# schChaves.net
KiCad netlist of a schematic drawn in Altium Designer
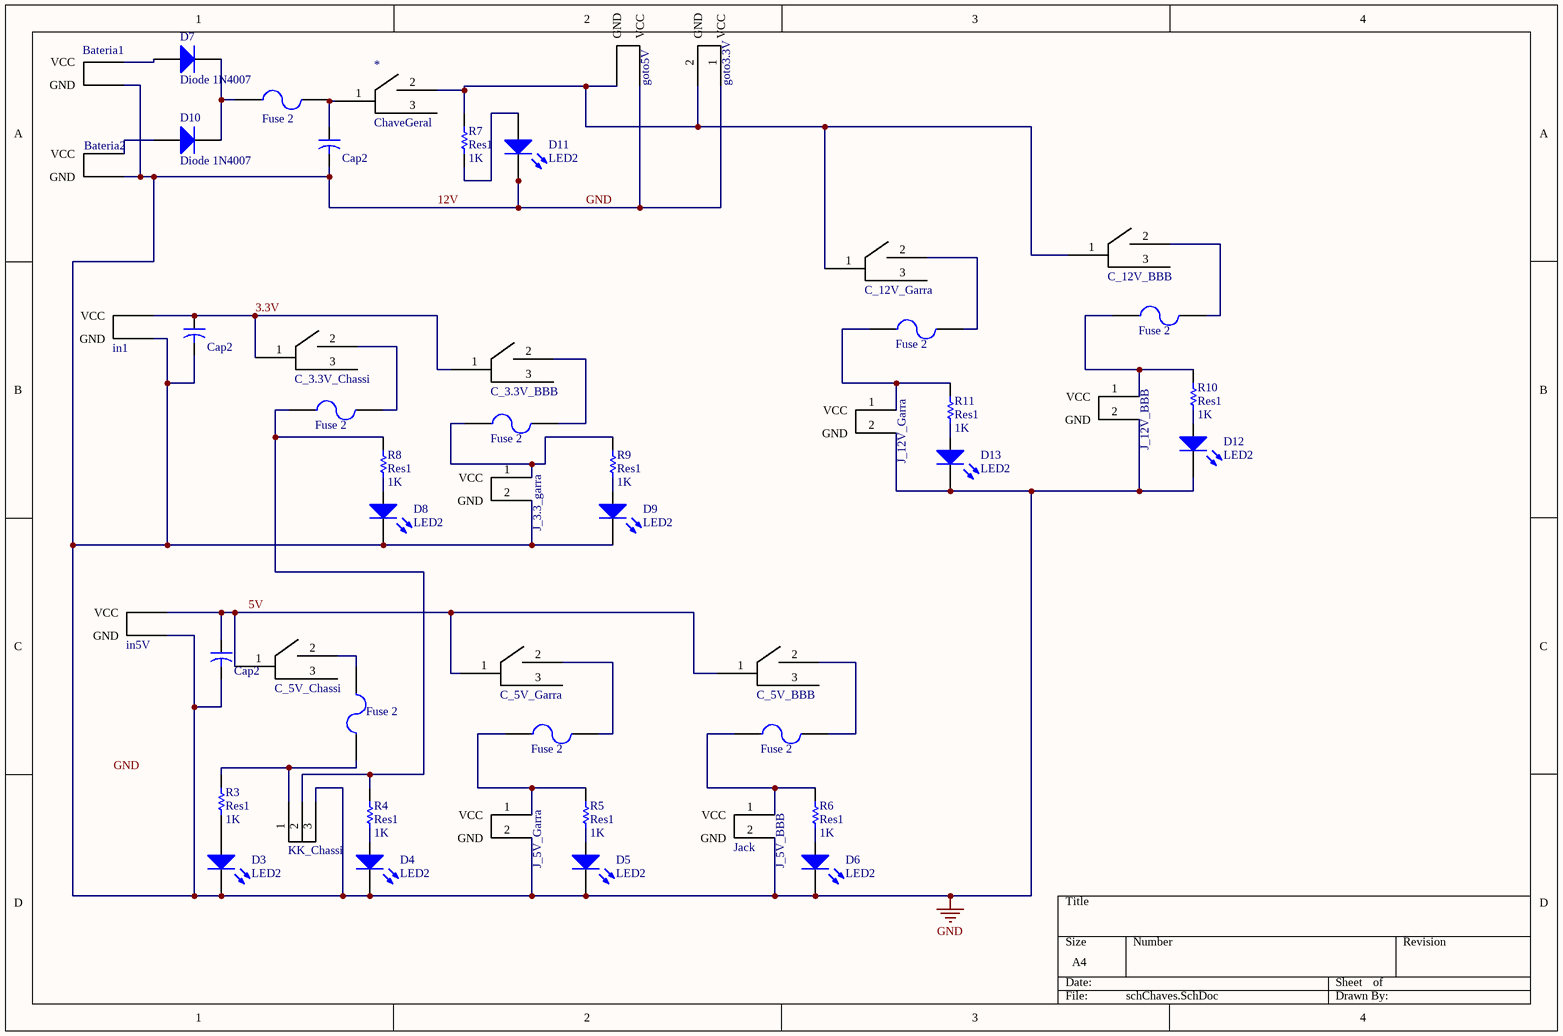
[diagram p0: schChaves.SchDoc]

(export (version "E")
  (design (tool "Eeschema 10.0.6"))
  (components
    (comp (ref "*")
      (value "ChaveGeral")
      (footprint "Chave")
      (libsource (lib "Componentes_Open") (part "Chave"))
    )
    (comp (ref "Bateria1")
      (value "Jack")
      (footprint "JACK J4")
      (libsource (lib "Componentes_Open") (part "Jack"))
    )
    (comp (ref "Bateria2")
      (value "Jack")
      (footprint "JACK J4")
      (libsource (lib "Componentes_Open") (part "Jack"))
    )
    (comp (ref "C_3.3V_BBB")
      (value "Chave")
      (footprint "Chave")
      (libsource (lib "Componentes_Open") (part "Chave"))
    )
    (comp (ref "C_3.3V_Chassi")
      (value "Chave")
      (footprint "Chave")
      (libsource (lib "Componentes_Open") (part "Chave"))
    )
    (comp (ref "C_5V_BBB")
      (value "Chave")
      (footprint "Chave")
      (libsource (lib "Componentes_Open") (part "Chave"))
    )
    (comp (ref "C_5V_Chassi")
      (value "Chave")
      (footprint "Chave")
      (libsource (lib "Componentes_Open") (part "Chave"))
    )
    (comp (ref "C_5V_Garra")
      (value "Chave")
      (footprint "Chave")
      (libsource (lib "Componentes_Open") (part "Chave"))
    )
    (comp (ref "C_12V_BBB")
      (value "Chave")
      (footprint "Chave")
      (libsource (lib "Componentes_Open") (part "Chave"))
    )
    (comp (ref "C_12V_Garra")
      (value "Chave")
      (footprint "Chave")
      (libsource (lib "Componentes_Open") (part "Chave"))
    )
    (comp (ref "C_parrudo")
      (value "Cap2")
      (footprint "CAPR5-4X5")
      (description "Capacitor")
      (fields (field (name "PUBLISHER") "Altium Limited"))
      (libsource (lib "Miscellaneous Devices") (part "Cap2"))
    )
    (comp (ref "C_parrudo1")
      (value "Cap2")
      (footprint "CAPR5-4X5")
      (description "Capacitor")
      (fields (field (name "PUBLISHER") "Altium Limited"))
      (libsource (lib "Miscellaneous Devices") (part "Cap2"))
    )
    (comp (ref "C_parrudo2")
      (value "Cap2")
      (footprint "CAPR5-4X5")
      (description "Capacitor")
      (fields (field (name "PUBLISHER") "Altium Limited"))
      (libsource (lib "Miscellaneous Devices") (part "Cap2"))
    )
    (comp (ref "D3")
      (value "LED2")
      (footprint "2-vias")
      (description "Typical RED, GREEN, YELLOW, AMBER GaAs LED")
      (fields (field (name "PUBLISHER") "Altium Limited"))
      (libsource (lib "Miscellaneous Devices") (part "LED2"))
    )
    (comp (ref "D4")
      (value "LED2")
      (footprint "2-vias")
      (description "Typical RED, GREEN, YELLOW, AMBER GaAs LED")
      (fields (field (name "PUBLISHER") "Altium Limited"))
      (libsource (lib "Miscellaneous Devices") (part "LED2"))
    )
    (comp (ref "D5")
      (value "LED2")
      (footprint "2-vias")
      (description "Typical RED, GREEN, YELLOW, AMBER GaAs LED")
      (fields (field (name "PUBLISHER") "Altium Limited"))
      (libsource (lib "Miscellaneous Devices") (part "LED2"))
    )
    (comp (ref "D6")
      (value "LED2")
      (footprint "2-vias")
      (description "Typical RED, GREEN, YELLOW, AMBER GaAs LED")
      (fields (field (name "PUBLISHER") "Altium Limited"))
      (libsource (lib "Miscellaneous Devices") (part "LED2"))
    )
    (comp (ref "D7")
      (value "Diode 1N4007")
      (footprint "DO-41")
      (description "1 Amp General Purpose Rectifier")
      (fields (field (name "PUBLISHER") "Altium Limited"))
      (libsource (lib "Miscellaneous Devices") (part "Diode 1N4007"))
    )
    (comp (ref "D8")
      (value "LED2")
      (footprint "2-vias")
      (description "Typical RED, GREEN, YELLOW, AMBER GaAs LED")
      (fields (field (name "PUBLISHER") "Altium Limited"))
      (libsource (lib "Miscellaneous Devices") (part "LED2"))
    )
    (comp (ref "D9")
      (value "LED2")
      (footprint "2-vias")
      (description "Typical RED, GREEN, YELLOW, AMBER GaAs LED")
      (fields (field (name "PUBLISHER") "Altium Limited"))
      (libsource (lib "Miscellaneous Devices") (part "LED2"))
    )
    (comp (ref "D10")
      (value "Diode 1N4007")
      (footprint "DO-41")
      (description "1 Amp General Purpose Rectifier")
      (fields (field (name "PUBLISHER") "Altium Limited"))
      (libsource (lib "Miscellaneous Devices") (part "Diode 1N4007"))
    )
    (comp (ref "D11")
      (value "LED2")
      (footprint "2-vias")
      (description "Typical RED, GREEN, YELLOW, AMBER GaAs LED")
      (fields (field (name "PUBLISHER") "Altium Limited"))
      (libsource (lib "Miscellaneous Devices") (part "LED2"))
    )
    (comp (ref "D12")
      (value "LED2")
      (footprint "2-vias")
      (description "Typical RED, GREEN, YELLOW, AMBER GaAs LED")
      (fields (field (name "PUBLISHER") "Altium Limited"))
      (libsource (lib "Miscellaneous Devices") (part "LED2"))
    )
    (comp (ref "D13")
      (value "LED2")
      (footprint "2-vias")
      (description "Typical RED, GREEN, YELLOW, AMBER GaAs LED")
      (fields (field (name "PUBLISHER") "Altium Limited"))
      (libsource (lib "Miscellaneous Devices") (part "LED2"))
    )
    (comp (ref "F1")
      (value "Fuse 2")
      (footprint "AXIAL-0.9")
      (description "Fuse")
      (fields (field (name "PUBLISHER") "Altium Limited"))
      (libsource (lib "Miscellaneous Devices") (part "Fuse 2"))
    )
    (comp (ref "F2")
      (value "Fuse 2")
      (footprint "AXIAL-0.9")
      (description "Fuse")
      (fields (field (name "PUBLISHER") "Altium Limited"))
      (libsource (lib "Miscellaneous Devices") (part "Fuse 2"))
    )
    (comp (ref "F3")
      (value "Fuse 2")
      (footprint "AXIAL-0.9")
      (description "Fuse")
      (fields (field (name "PUBLISHER") "Altium Limited"))
      (libsource (lib "Miscellaneous Devices") (part "Fuse 2"))
    )
    (comp (ref "F4")
      (value "Fuse 2")
      (footprint "AXIAL-0.9")
      (description "Fuse")
      (fields (field (name "PUBLISHER") "Altium Limited"))
      (libsource (lib "Miscellaneous Devices") (part "Fuse 2"))
    )
    (comp (ref "F5")
      (value "Fuse 2")
      (footprint "AXIAL-0.9")
      (description "Fuse")
      (fields (field (name "PUBLISHER") "Altium Limited"))
      (libsource (lib "Miscellaneous Devices") (part "Fuse 2"))
    )
    (comp (ref "F6")
      (value "Fuse 2")
      (footprint "AXIAL-0.9")
      (description "Fuse")
      (fields (field (name "PUBLISHER") "Altium Limited"))
      (libsource (lib "Miscellaneous Devices") (part "Fuse 2"))
    )
    (comp (ref "F7")
      (value "Fuse 2")
      (footprint "AXIAL-0.9")
      (description "Fuse")
      (fields (field (name "PUBLISHER") "Altium Limited"))
      (libsource (lib "Miscellaneous Devices") (part "Fuse 2"))
    )
    (comp (ref "F8")
      (value "Fuse 2")
      (footprint "AXIAL-0.9")
      (description "Fuse")
      (fields (field (name "PUBLISHER") "Altium Limited"))
      (libsource (lib "Miscellaneous Devices") (part "Fuse 2"))
    )
    (comp (ref "goto3.3V") (value "Jack") (footprint "JACK J4") (libsource (lib "") (part "Jack_1")))
    (comp (ref "goto5V")
      (value "Jack")
      (footprint "JACK J4")
      (libsource (lib "Componentes_Open") (part "Jack"))
    )
    (comp (ref "in1") (value "Jack") (footprint "JACK J4") (libsource (lib "Componentes_Open") (part "Jack")))
    (comp (ref "in5V")
      (value "Jack")
      (footprint "JACK J4")
      (libsource (lib "Componentes_Open") (part "Jack"))
    )
    (comp (ref "J_3.3_garra") (value "Jack") (footprint "JACK J4") (libsource (lib "") (part "Jack_1")))
    (comp (ref "J_5V_BBB") (value "Jack") (footprint "JACK J4") (libsource (lib "") (part "Jack_1")))
    (comp (ref "J_5V_Garra") (value "Jack") (footprint "JACK J4") (libsource (lib "") (part "Jack_1")))
    (comp (ref "J_12V_BBB") (value "Jack") (footprint "JACK J4") (libsource (lib "") (part "Jack_1")))
    (comp (ref "J_12V_Garra") (value "Jack") (footprint "JACK J4") (libsource (lib "") (part "Jack_1")))
    (comp (ref "KK_Chassi")
      (value "KK3")
      (footprint "3-vias")
      (libsource (lib "Componentes_Open") (part "KK3Vias"))
    )
    (comp (ref "R3")
      (value "Res1")
      (footprint "AXIAL-0.3")
      (description "Resistor")
      (fields (field (name "ALTIUM_VALUE") "1K") (field (name "PUBLISHER") "Altium Limited"))
      (libsource (lib "Miscellaneous Devices") (part "Res1"))
    )
    (comp (ref "R4")
      (value "Res1")
      (footprint "AXIAL-0.3")
      (description "Resistor")
      (fields (field (name "ALTIUM_VALUE") "1K") (field (name "PUBLISHER") "Altium Limited"))
      (libsource (lib "Miscellaneous Devices") (part "Res1"))
    )
    (comp (ref "R5")
      (value "Res1")
      (footprint "AXIAL-0.3")
      (description "Resistor")
      (fields (field (name "ALTIUM_VALUE") "1K") (field (name "PUBLISHER") "Altium Limited"))
      (libsource (lib "Miscellaneous Devices") (part "Res1"))
    )
    (comp (ref "R6")
      (value "Res1")
      (footprint "AXIAL-0.3")
      (description "Resistor")
      (fields (field (name "ALTIUM_VALUE") "1K") (field (name "PUBLISHER") "Altium Limited"))
      (libsource (lib "Miscellaneous Devices") (part "Res1"))
    )
    (comp (ref "R7")
      (value "Res1")
      (footprint "AXIAL-0.3")
      (description "Resistor")
      (fields (field (name "ALTIUM_VALUE") "1K") (field (name "PUBLISHER") "Altium Limited"))
      (libsource (lib "Miscellaneous Devices") (part "Res1"))
    )
    (comp (ref "R8")
      (value "Res1")
      (footprint "AXIAL-0.3")
      (description "Resistor")
      (fields (field (name "ALTIUM_VALUE") "1K") (field (name "PUBLISHER") "Altium Limited"))
      (libsource (lib "Miscellaneous Devices") (part "Res1"))
    )
    (comp (ref "R9")
      (value "Res1")
      (footprint "AXIAL-0.3")
      (description "Resistor")
      (fields (field (name "ALTIUM_VALUE") "1K") (field (name "PUBLISHER") "Altium Limited"))
      (libsource (lib "Miscellaneous Devices") (part "Res1"))
    )
    (comp (ref "R10")
      (value "Res1")
      (footprint "AXIAL-0.3")
      (description "Resistor")
      (fields (field (name "ALTIUM_VALUE") "1K") (field (name "PUBLISHER") "Altium Limited"))
      (libsource (lib "Miscellaneous Devices") (part "Res1"))
    )
    (comp (ref "R11")
      (value "Res1")
      (footprint "AXIAL-0.3")
      (description "Resistor")
      (fields (field (name "ALTIUM_VALUE") "1K") (field (name "PUBLISHER") "Altium Limited"))
      (libsource (lib "Miscellaneous Devices") (part "Res1"))
    )
  )
  (nets
    (net (code "1") (name "/3.3V") (class "Default")
      (node (ref "C_3.3V_BBB") (pin "1") (pinfunction "Comum_1") (pintype "passive"))
      (node (ref "C_3.3V_Chassi") (pin "1") (pinfunction "Comum_1") (pintype "passive"))
      (node (ref "C_parrudo1") (pin "1") (pinfunction "1_1") (pintype "passive"))
      (node (ref "in1") (pin "1") (pinfunction "VCC_1") (pintype "passive"))
    )
    (net (code "2") (name "/5V") (class "Default")
      (node (ref "C_5V_BBB") (pin "1") (pinfunction "Comum_1") (pintype "passive"))
      (node (ref "C_5V_Chassi") (pin "1") (pinfunction "Comum_1") (pintype "passive"))
      (node (ref "C_5V_Garra") (pin "1") (pinfunction "Comum_1") (pintype "passive"))
      (node (ref "C_parrudo2") (pin "1") (pinfunction "1_1") (pintype "passive"))
      (node (ref "in5V") (pin "1") (pinfunction "VCC_1") (pintype "passive"))
    )
    (net (code "3") (name "GND") (class "Default")
      (node (ref "Bateria1") (pin "2") (pinfunction "GND_2") (pintype "passive"))
      (node (ref "Bateria2") (pin "2") (pinfunction "GND_2") (pintype "passive"))
      (node (ref "C_parrudo") (pin "2") (pinfunction "2_2") (pintype "passive"))
      (node (ref "C_parrudo1") (pin "2") (pinfunction "2_2") (pintype "passive"))
      (node (ref "C_parrudo2") (pin "2") (pinfunction "2_2") (pintype "passive"))
      (node (ref "D11") (pin "2") (pinfunction "K_2") (pintype "passive"))
      (node (ref "D12") (pin "2") (pinfunction "K_2") (pintype "passive"))
      (node (ref "D13") (pin "2") (pinfunction "K_2") (pintype "passive"))
      (node (ref "D3") (pin "2") (pinfunction "K_2") (pintype "passive"))
      (node (ref "D4") (pin "2") (pinfunction "K_2") (pintype "passive"))
      (node (ref "D5") (pin "2") (pinfunction "K_2") (pintype "passive"))
      (node (ref "D6") (pin "2") (pinfunction "K_2") (pintype "passive"))
      (node (ref "D8") (pin "2") (pinfunction "K_2") (pintype "passive"))
      (node (ref "D9") (pin "2") (pinfunction "K_2") (pintype "passive"))
      (node (ref "J_12V_BBB") (pin "2") (pinfunction "GND_2") (pintype "passive"))
      (node (ref "J_12V_Garra") (pin "2") (pinfunction "GND_2") (pintype "passive"))
      (node (ref "J_3.3_garra") (pin "2") (pinfunction "GND_2") (pintype "passive"))
      (node (ref "J_5V_BBB") (pin "2") (pinfunction "GND_2") (pintype "passive"))
      (node (ref "J_5V_Garra") (pin "2") (pinfunction "GND_2") (pintype "passive"))
      (node (ref "KK_Chassi") (pin "3") (pinfunction "3_3") (pintype "passive"))
      (node (ref "goto3.3V") (pin "1") (pinfunction "VCC_1") (pintype "passive"))
      (node (ref "goto5V") (pin "1") (pinfunction "VCC_1") (pintype "passive"))
      (node (ref "in1") (pin "2") (pinfunction "GND_2") (pintype "passive"))
      (node (ref "in5V") (pin "2") (pinfunction "GND_2") (pintype "passive"))
    )
    (net (code "4") (name "Net-(*-Comum)") (class "Default")
      (node (ref "*") (pin "1") (pinfunction "Comum_1") (pintype "passive"))
      (node (ref "C_parrudo") (pin "1") (pinfunction "1_1") (pintype "passive"))
      (node (ref "F1") (pin "2") (pinfunction "2_2") (pintype "passive"))
    )
    (net (code "5") (name "Net-(*-N.A.)") (class "Default")
      (node (ref "*") (pin "2") (pinfunction "N.A._2") (pintype "passive"))
      (node (ref "C_12V_BBB") (pin "1") (pinfunction "Comum_1") (pintype "passive"))
      (node (ref "C_12V_Garra") (pin "1") (pinfunction "Comum_1") (pintype "passive"))
      (node (ref "R7") (pin "2") (pinfunction "2_2") (pintype "passive"))
      (node (ref "goto3.3V") (pin "2") (pinfunction "GND_2") (pintype "passive"))
      (node (ref "goto5V") (pin "2") (pinfunction "GND_2") (pintype "passive"))
    )
    (net (code "6") (name "Net-(Bateria1-VCC)") (class "Default")
      (node (ref "Bateria1") (pin "1") (pinfunction "VCC_1") (pintype "passive"))
      (node (ref "D7") (pin "1") (pinfunction "A_1") (pintype "passive"))
    )
    (net (code "7") (name "Net-(Bateria2-VCC)") (class "Default")
      (node (ref "Bateria2") (pin "1") (pinfunction "VCC_1") (pintype "passive"))
      (node (ref "D10") (pin "1") (pinfunction "A_1") (pintype "passive"))
    )
    (net (code "8") (name "Net-(C_3.3V_BBB-N.A.)") (class "Default")
      (node (ref "C_3.3V_BBB") (pin "2") (pinfunction "N.A._2") (pintype "passive"))
      (node (ref "F3") (pin "2") (pinfunction "2_2") (pintype "passive"))
    )
    (net (code "9") (name "Net-(C_3.3V_Chassi-N.A.)") (class "Default")
      (node (ref "C_3.3V_Chassi") (pin "2") (pinfunction "N.A._2") (pintype "passive"))
      (node (ref "F2") (pin "2") (pinfunction "2_2") (pintype "passive"))
    )
    (net (code "10") (name "Net-(C_5V_BBB-N.A.)") (class "Default")
      (node (ref "C_5V_BBB") (pin "2") (pinfunction "N.A._2") (pintype "passive"))
      (node (ref "F6") (pin "2") (pinfunction "2_2") (pintype "passive"))
    )
    (net (code "11") (name "Net-(C_5V_Chassi-N.A.)") (class "Default")
      (node (ref "C_5V_Chassi") (pin "2") (pinfunction "N.A._2") (pintype "passive"))
      (node (ref "F4") (pin "1") (pinfunction "1_1") (pintype "passive"))
    )
    (net (code "12") (name "Net-(C_5V_Garra-N.A.)") (class "Default")
      (node (ref "C_5V_Garra") (pin "2") (pinfunction "N.A._2") (pintype "passive"))
      (node (ref "F5") (pin "2") (pinfunction "2_2") (pintype "passive"))
    )
    (net (code "13") (name "Net-(C_12V_BBB-N.A.)") (class "Default")
      (node (ref "C_12V_BBB") (pin "2") (pinfunction "N.A._2") (pintype "passive"))
      (node (ref "F7") (pin "2") (pinfunction "2_2") (pintype "passive"))
    )
    (net (code "14") (name "Net-(C_12V_Garra-N.A.)") (class "Default")
      (node (ref "C_12V_Garra") (pin "2") (pinfunction "N.A._2") (pintype "passive"))
      (node (ref "F8") (pin "2") (pinfunction "2_2") (pintype "passive"))
    )
    (net (code "15") (name "Net-(D3-A)") (class "Default")
      (node (ref "D3") (pin "1") (pinfunction "A_1") (pintype "passive"))
      (node (ref "R3") (pin "1") (pinfunction "1_1") (pintype "passive"))
    )
    (net (code "16") (name "Net-(D4-A)") (class "Default")
      (node (ref "D4") (pin "1") (pinfunction "A_1") (pintype "passive"))
      (node (ref "R4") (pin "1") (pinfunction "1_1") (pintype "passive"))
    )
    (net (code "17") (name "Net-(D5-A)") (class "Default")
      (node (ref "D5") (pin "1") (pinfunction "A_1") (pintype "passive"))
      (node (ref "R5") (pin "1") (pinfunction "1_1") (pintype "passive"))
    )
    (net (code "18") (name "Net-(D6-A)") (class "Default")
      (node (ref "D6") (pin "1") (pinfunction "A_1") (pintype "passive"))
      (node (ref "R6") (pin "1") (pinfunction "1_1") (pintype "passive"))
    )
    (net (code "19") (name "Net-(D8-A)") (class "Default")
      (node (ref "D8") (pin "1") (pinfunction "A_1") (pintype "passive"))
      (node (ref "R8") (pin "1") (pinfunction "1_1") (pintype "passive"))
    )
    (net (code "20") (name "Net-(D9-A)") (class "Default")
      (node (ref "D9") (pin "1") (pinfunction "A_1") (pintype "passive"))
      (node (ref "R9") (pin "1") (pinfunction "1_1") (pintype "passive"))
    )
    (net (code "21") (name "Net-(D10-K)") (class "Default")
      (node (ref "D10") (pin "2") (pinfunction "K_2") (pintype "passive"))
      (node (ref "D7") (pin "2") (pinfunction "K_2") (pintype "passive"))
      (node (ref "F1") (pin "1") (pinfunction "1_1") (pintype "passive"))
    )
    (net (code "22") (name "Net-(D11-A)") (class "Default")
      (node (ref "D11") (pin "1") (pinfunction "A_1") (pintype "passive"))
      (node (ref "R7") (pin "1") (pinfunction "1_1") (pintype "passive"))
    )
    (net (code "23") (name "Net-(D12-A)") (class "Default")
      (node (ref "D12") (pin "1") (pinfunction "A_1") (pintype "passive"))
      (node (ref "R10") (pin "1") (pinfunction "1_1") (pintype "passive"))
    )
    (net (code "24") (name "Net-(D13-A)") (class "Default")
      (node (ref "D13") (pin "1") (pinfunction "A_1") (pintype "passive"))
      (node (ref "R11") (pin "1") (pinfunction "1_1") (pintype "passive"))
    )
    (net (code "25") (name "Net-(F2-Pad1)") (class "Default")
      (node (ref "F2") (pin "1") (pinfunction "1_1") (pintype "passive"))
      (node (ref "KK_Chassi") (pin "2") (pinfunction "2_2") (pintype "passive"))
      (node (ref "R4") (pin "2") (pinfunction "2_2") (pintype "passive"))
      (node (ref "R8") (pin "2") (pinfunction "2_2") (pintype "passive"))
    )
    (net (code "26") (name "Net-(F4-Pad2)") (class "Default")
      (node (ref "F4") (pin "2") (pinfunction "2_2") (pintype "passive"))
      (node (ref "KK_Chassi") (pin "1") (pinfunction "1_1") (pintype "passive"))
      (node (ref "R3") (pin "2") (pinfunction "2_2") (pintype "passive"))
    )
    (net (code "27") (name "Net-(J_3.3_garra-VCC)") (class "Default")
      (node (ref "F3") (pin "1") (pinfunction "1_1") (pintype "passive"))
      (node (ref "J_3.3_garra") (pin "1") (pinfunction "VCC_1") (pintype "passive"))
      (node (ref "R9") (pin "2") (pinfunction "2_2") (pintype "passive"))
    )
    (net (code "28") (name "Net-(J_5V_BBB-VCC)") (class "Default")
      (node (ref "F6") (pin "1") (pinfunction "1_1") (pintype "passive"))
      (node (ref "J_5V_BBB") (pin "1") (pinfunction "VCC_1") (pintype "passive"))
      (node (ref "R6") (pin "2") (pinfunction "2_2") (pintype "passive"))
    )
    (net (code "29") (name "Net-(J_5V_Garra-VCC)") (class "Default")
      (node (ref "F5") (pin "1") (pinfunction "1_1") (pintype "passive"))
      (node (ref "J_5V_Garra") (pin "1") (pinfunction "VCC_1") (pintype "passive"))
      (node (ref "R5") (pin "2") (pinfunction "2_2") (pintype "passive"))
    )
    (net (code "30") (name "Net-(J_12V_BBB-VCC)") (class "Default")
      (node (ref "F7") (pin "1") (pinfunction "1_1") (pintype "passive"))
      (node (ref "J_12V_BBB") (pin "1") (pinfunction "VCC_1") (pintype "passive"))
      (node (ref "R10") (pin "2") (pinfunction "2_2") (pintype "passive"))
    )
    (net (code "31") (name "Net-(J_12V_Garra-VCC)") (class "Default")
      (node (ref "F8") (pin "1") (pinfunction "1_1") (pintype "passive"))
      (node (ref "J_12V_Garra") (pin "1") (pinfunction "VCC_1") (pintype "passive"))
      (node (ref "R11") (pin "2") (pinfunction "2_2") (pintype "passive"))
    )
    (net (code "32") (name "unconnected-(*-N.F-Pad3)") (class "Default")
      (node (ref "*") (pin "3") (pinfunction "N.F_3") (pintype "passive"))
    )
    (net (code "33") (name "unconnected-(C_3.3V_BBB-N.F-Pad3)") (class "Default")
      (node (ref "C_3.3V_BBB") (pin "3") (pinfunction "N.F_3") (pintype "passive"))
    )
    (net (code "34") (name "unconnected-(C_3.3V_Chassi-N.F-Pad3)") (class "Default")
      (node (ref "C_3.3V_Chassi") (pin "3") (pinfunction "N.F_3") (pintype "passive"))
    )
    (net (code "35") (name "unconnected-(C_5V_BBB-N.F-Pad3)") (class "Default")
      (node (ref "C_5V_BBB") (pin "3") (pinfunction "N.F_3") (pintype "passive"))
    )
    (net (code "36") (name "unconnected-(C_5V_Chassi-N.F-Pad3)") (class "Default")
      (node (ref "C_5V_Chassi") (pin "3") (pinfunction "N.F_3") (pintype "passive"))
    )
    (net (code "37") (name "unconnected-(C_5V_Garra-N.F-Pad3)") (class "Default")
      (node (ref "C_5V_Garra") (pin "3") (pinfunction "N.F_3") (pintype "passive"))
    )
    (net (code "38") (name "unconnected-(C_12V_BBB-N.F-Pad3)") (class "Default")
      (node (ref "C_12V_BBB") (pin "3") (pinfunction "N.F_3") (pintype "passive"))
    )
    (net (code "39") (name "unconnected-(C_12V_Garra-N.F-Pad3)") (class "Default")
      (node (ref "C_12V_Garra") (pin "3") (pinfunction "N.F_3") (pintype "passive"))
    )
  )
)
